# leds.net
KiCad netlist of a schematic drawn in Altium Designer
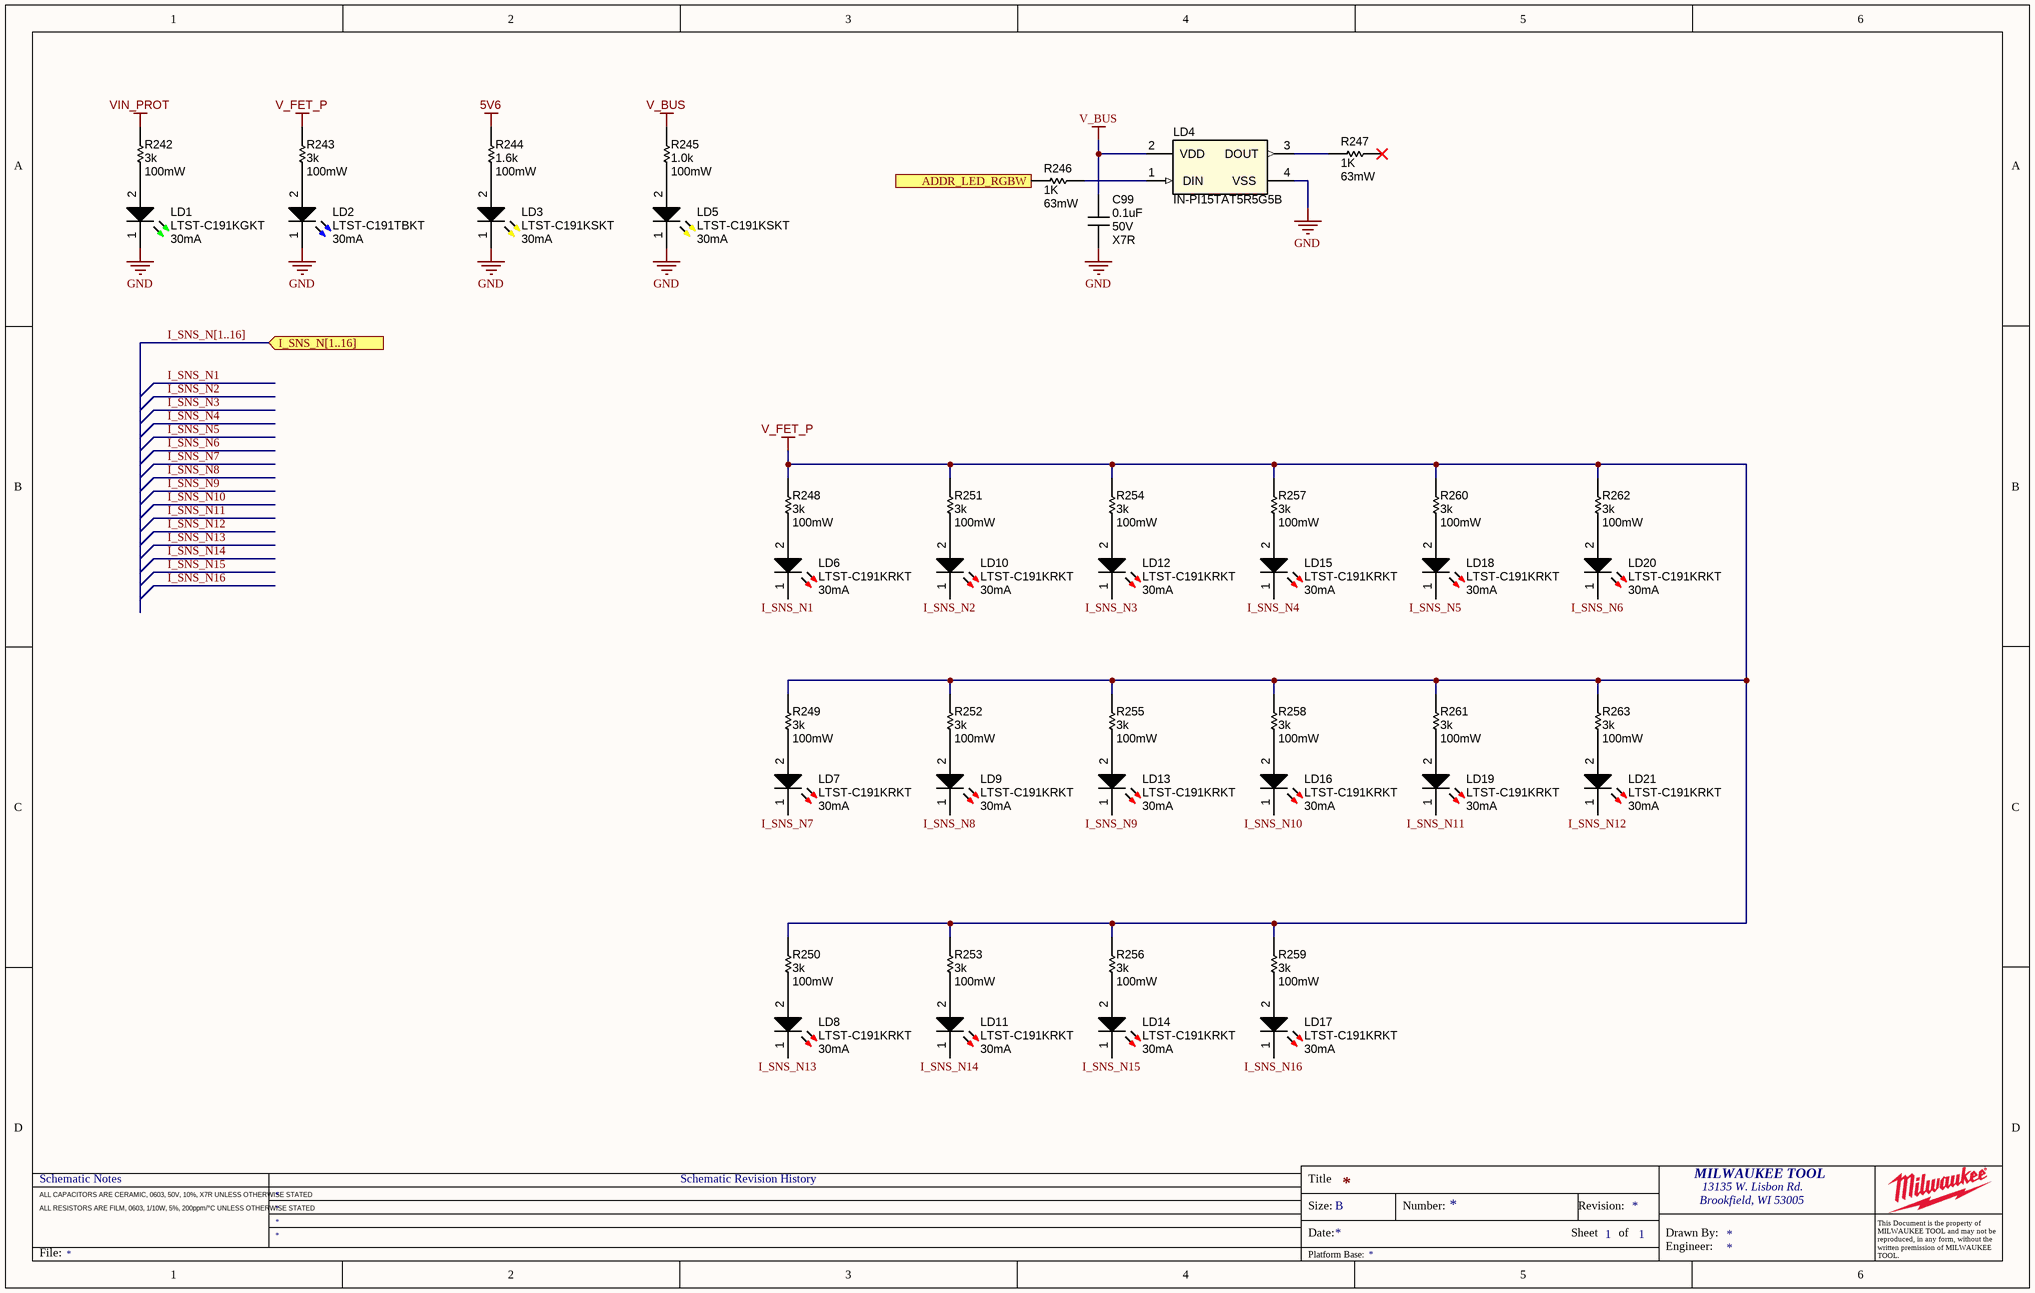
[diagram p0: leds.SchDoc]

(export (version "E")
  (design (tool "Eeschema 10.0.6"))
  (components
    (comp (ref "C99")
      (value "0.1uF")
      (footprint "CAPC1005X06N")
      (description "CAP CER SMD 0.1UF 50V X7R 0402")
      (fields
        (field (name "TOLERANCE") "10%")
        (field (name "MFR") "Murata Electronics")
        (field (name "VOLTAGE RATING") "50V")
        (field (name "TEMP COEFF") "X7R")
      )
      (libsource (lib "General_Library") (part "CMP-004-0076"))
    )
    (comp (ref "LD1")
      (value "LTST-C191KGKT")
      (footprint "LED_0603_GREEN")
      (description "LED GREEN CLEAR 0603 SMD")
      (fields
        (field (name "MFR") "Lite-On Inc.")
        (field (name "VOLTAGE") "2V")
        (field (name "CURRENT RATING") "30mA")
      )
      (libsource (lib "General_Library") (part "CMP-012-0014"))
    )
    (comp (ref "LD2")
      (value "LTST-C191TBKT")
      (footprint "LED_0603_BLUE")
      (description "LED BLUE CLEAR 0603 SMD")
      (fields
        (field (name "MFR") "Lite-On Inc.")
        (field (name "VOLTAGE") "2V")
        (field (name "CURRENT RATING") "30mA")
      )
      (libsource (lib "General_Library") (part "CMP-012-0016"))
    )
    (comp (ref "LD3")
      (value "LTST-C191KSKT")
      (footprint "LED_0603_YELLOW")
      (description "LED YELLOW CLEAR 0603 SMD")
      (fields
        (field (name "MFR") "Lite-On Inc.")
        (field (name "VOLTAGE") "2V")
        (field (name "CURRENT RATING") "30mA")
      )
      (libsource (lib "General_Library") (part "CMP-012-0015"))
    )
    (comp (ref "LD4")
      (value "IN-PI15TAT5R5G5B")
      (footprint "LED_INOLUX_IN-PI15TAT5R5G5B")
      (description "LED ADDRESSABLE RGB 1.50mm x 1.50mm")
      (fields (field (name "MFR") "Inolux"))
      (libsource (lib "General_Library") (part "CMP-012-0023"))
    )
    (comp (ref "LD5")
      (value "LTST-C191KSKT")
      (footprint "LED_0603_YELLOW")
      (description "LED YELLOW CLEAR 0603 SMD")
      (fields
        (field (name "MFR") "Lite-On Inc.")
        (field (name "VOLTAGE") "2V")
        (field (name "CURRENT RATING") "30mA")
      )
      (libsource (lib "General_Library") (part "CMP-012-0015"))
    )
    (comp (ref "LD6")
      (value "LTST-C191KRKT")
      (footprint "LED_0603_RED")
      (description "LED RED CLEAR 0603 SMD")
      (fields
        (field (name "MFR") "Lite-On Inc.")
        (field (name "VOLTAGE") "2V")
        (field (name "CURRENT RATING") "30mA")
      )
      (libsource (lib "General_Library") (part "CMP-012-0013"))
    )
    (comp (ref "LD7")
      (value "LTST-C191KRKT")
      (footprint "LED_0603_RED")
      (description "LED RED CLEAR 0603 SMD")
      (fields
        (field (name "MFR") "Lite-On Inc.")
        (field (name "VOLTAGE") "2V")
        (field (name "CURRENT RATING") "30mA")
      )
      (libsource (lib "General_Library") (part "CMP-012-0013"))
    )
    (comp (ref "LD8")
      (value "LTST-C191KRKT")
      (footprint "LED_0603_RED")
      (description "LED RED CLEAR 0603 SMD")
      (fields
        (field (name "MFR") "Lite-On Inc.")
        (field (name "VOLTAGE") "2V")
        (field (name "CURRENT RATING") "30mA")
      )
      (libsource (lib "General_Library") (part "CMP-012-0013"))
    )
    (comp (ref "LD9")
      (value "LTST-C191KRKT")
      (footprint "LED_0603_RED")
      (description "LED RED CLEAR 0603 SMD")
      (fields
        (field (name "MFR") "Lite-On Inc.")
        (field (name "VOLTAGE") "2V")
        (field (name "CURRENT RATING") "30mA")
      )
      (libsource (lib "General_Library") (part "CMP-012-0013"))
    )
    (comp (ref "LD10")
      (value "LTST-C191KRKT")
      (footprint "LED_0603_RED")
      (description "LED RED CLEAR 0603 SMD")
      (fields
        (field (name "MFR") "Lite-On Inc.")
        (field (name "VOLTAGE") "2V")
        (field (name "CURRENT RATING") "30mA")
      )
      (libsource (lib "General_Library") (part "CMP-012-0013"))
    )
    (comp (ref "LD11")
      (value "LTST-C191KRKT")
      (footprint "LED_0603_RED")
      (description "LED RED CLEAR 0603 SMD")
      (fields
        (field (name "MFR") "Lite-On Inc.")
        (field (name "VOLTAGE") "2V")
        (field (name "CURRENT RATING") "30mA")
      )
      (libsource (lib "General_Library") (part "CMP-012-0013"))
    )
    (comp (ref "LD12")
      (value "LTST-C191KRKT")
      (footprint "LED_0603_RED")
      (description "LED RED CLEAR 0603 SMD")
      (fields
        (field (name "MFR") "Lite-On Inc.")
        (field (name "VOLTAGE") "2V")
        (field (name "CURRENT RATING") "30mA")
      )
      (libsource (lib "General_Library") (part "CMP-012-0013"))
    )
    (comp (ref "LD13")
      (value "LTST-C191KRKT")
      (footprint "LED_0603_RED")
      (description "LED RED CLEAR 0603 SMD")
      (fields
        (field (name "MFR") "Lite-On Inc.")
        (field (name "VOLTAGE") "2V")
        (field (name "CURRENT RATING") "30mA")
      )
      (libsource (lib "General_Library") (part "CMP-012-0013"))
    )
    (comp (ref "LD14")
      (value "LTST-C191KRKT")
      (footprint "LED_0603_RED")
      (description "LED RED CLEAR 0603 SMD")
      (fields
        (field (name "MFR") "Lite-On Inc.")
        (field (name "VOLTAGE") "2V")
        (field (name "CURRENT RATING") "30mA")
      )
      (libsource (lib "General_Library") (part "CMP-012-0013"))
    )
    (comp (ref "LD15")
      (value "LTST-C191KRKT")
      (footprint "LED_0603_RED")
      (description "LED RED CLEAR 0603 SMD")
      (fields
        (field (name "MFR") "Lite-On Inc.")
        (field (name "VOLTAGE") "2V")
        (field (name "CURRENT RATING") "30mA")
      )
      (libsource (lib "General_Library") (part "CMP-012-0013"))
    )
    (comp (ref "LD16")
      (value "LTST-C191KRKT")
      (footprint "LED_0603_RED")
      (description "LED RED CLEAR 0603 SMD")
      (fields
        (field (name "MFR") "Lite-On Inc.")
        (field (name "VOLTAGE") "2V")
        (field (name "CURRENT RATING") "30mA")
      )
      (libsource (lib "General_Library") (part "CMP-012-0013"))
    )
    (comp (ref "LD17")
      (value "LTST-C191KRKT")
      (footprint "LED_0603_RED")
      (description "LED RED CLEAR 0603 SMD")
      (fields
        (field (name "MFR") "Lite-On Inc.")
        (field (name "VOLTAGE") "2V")
        (field (name "CURRENT RATING") "30mA")
      )
      (libsource (lib "General_Library") (part "CMP-012-0013"))
    )
    (comp (ref "LD18")
      (value "LTST-C191KRKT")
      (footprint "LED_0603_RED")
      (description "LED RED CLEAR 0603 SMD")
      (fields
        (field (name "MFR") "Lite-On Inc.")
        (field (name "VOLTAGE") "2V")
        (field (name "CURRENT RATING") "30mA")
      )
      (libsource (lib "General_Library") (part "CMP-012-0013"))
    )
    (comp (ref "LD19")
      (value "LTST-C191KRKT")
      (footprint "LED_0603_RED")
      (description "LED RED CLEAR 0603 SMD")
      (fields
        (field (name "MFR") "Lite-On Inc.")
        (field (name "VOLTAGE") "2V")
        (field (name "CURRENT RATING") "30mA")
      )
      (libsource (lib "General_Library") (part "CMP-012-0013"))
    )
    (comp (ref "LD20")
      (value "LTST-C191KRKT")
      (footprint "LED_0603_RED")
      (description "LED RED CLEAR 0603 SMD")
      (fields
        (field (name "MFR") "Lite-On Inc.")
        (field (name "VOLTAGE") "2V")
        (field (name "CURRENT RATING") "30mA")
      )
      (libsource (lib "General_Library") (part "CMP-012-0013"))
    )
    (comp (ref "LD21")
      (value "LTST-C191KRKT")
      (footprint "LED_0603_RED")
      (description "LED RED CLEAR 0603 SMD")
      (fields
        (field (name "MFR") "Lite-On Inc.")
        (field (name "VOLTAGE") "2V")
        (field (name "CURRENT RATING") "30mA")
      )
      (libsource (lib "General_Library") (part "CMP-012-0013"))
    )
    (comp (ref "R242")
      (value "3k")
      (footprint "RESC1608X06N")
      (description "RES SMD 3K OHM 1% 1/10W 0603")
      (fields
        (field (name "MFR") "Panasonic Electronic Components")
        (field (name "TOLERANCE") "1%")
        (field (name "WATTAGE") "100mW")
      )
      (libsource (lib "General_Library") (part "CMP-025-0012"))
    )
    (comp (ref "R243")
      (value "3k")
      (footprint "RESC1608X06N")
      (description "RES SMD 3K OHM 1% 1/10W 0603")
      (fields
        (field (name "MFR") "Panasonic Electronic Components")
        (field (name "TOLERANCE") "1%")
        (field (name "WATTAGE") "100mW")
      )
      (libsource (lib "General_Library") (part "CMP-025-0012"))
    )
    (comp (ref "R244")
      (value "1.6k")
      (footprint "RESC1608X06N")
      (description "RES SMD 1.6K OHM 1% 1/10W 0603")
      (fields
        (field (name "MFR") "Stackpole Electronics Inc")
        (field (name "TOLERANCE") "1%")
        (field (name "WATTAGE") "100mW")
      )
      (libsource (lib "General_Library") (part "CMP-025-0060"))
    )
    (comp (ref "R245")
      (value "1.0k")
      (footprint "RESC1608X06N")
      (description "RES SMD 1K OHM 1% 1/10W 0603")
      (fields
        (field (name "MFR") "Panasonic Electronic Components")
        (field (name "VOLTAGE") "75V")
        (field (name "WATTAGE") "100mW")
      )
      (libsource (lib "General_Library") (part "CMP-025-0097"))
    )
    (comp (ref "R246")
      (value "1K")
      (footprint "RESC1005X04N")
      (description "RES SMD 1K OHM 1% 1/16W 0402")
      (fields
        (field (name "TOLERANCE") "1%")
        (field (name "MFR") "Stackpole Electronics Inc")
        (field (name "WATTAGE") "63mW")
      )
      (libsource (lib "General_Library") (part "CMP-025-0154"))
    )
    (comp (ref "R247")
      (value "1K")
      (footprint "RESC1005X04N")
      (description "RES SMD 1K OHM 1% 1/16W 0402")
      (fields
        (field (name "TOLERANCE") "1%")
        (field (name "MFR") "Stackpole Electronics Inc")
        (field (name "WATTAGE") "63mW")
      )
      (libsource (lib "General_Library") (part "CMP-025-0154"))
    )
    (comp (ref "R248")
      (value "3k")
      (footprint "RESC1608X06N")
      (description "RES SMD 3K OHM 1% 1/10W 0603")
      (fields
        (field (name "MFR") "Panasonic Electronic Components")
        (field (name "TOLERANCE") "1%")
        (field (name "WATTAGE") "100mW")
      )
      (libsource (lib "General_Library") (part "CMP-025-0012"))
    )
    (comp (ref "R249")
      (value "3k")
      (footprint "RESC1608X06N")
      (description "RES SMD 3K OHM 1% 1/10W 0603")
      (fields
        (field (name "MFR") "Panasonic Electronic Components")
        (field (name "TOLERANCE") "1%")
        (field (name "WATTAGE") "100mW")
      )
      (libsource (lib "General_Library") (part "CMP-025-0012"))
    )
    (comp (ref "R250")
      (value "3k")
      (footprint "RESC1608X06N")
      (description "RES SMD 3K OHM 1% 1/10W 0603")
      (fields
        (field (name "MFR") "Panasonic Electronic Components")
        (field (name "TOLERANCE") "1%")
        (field (name "WATTAGE") "100mW")
      )
      (libsource (lib "General_Library") (part "CMP-025-0012"))
    )
    (comp (ref "R251")
      (value "3k")
      (footprint "RESC1608X06N")
      (description "RES SMD 3K OHM 1% 1/10W 0603")
      (fields
        (field (name "MFR") "Panasonic Electronic Components")
        (field (name "TOLERANCE") "1%")
        (field (name "WATTAGE") "100mW")
      )
      (libsource (lib "General_Library") (part "CMP-025-0012"))
    )
    (comp (ref "R252")
      (value "3k")
      (footprint "RESC1608X06N")
      (description "RES SMD 3K OHM 1% 1/10W 0603")
      (fields
        (field (name "MFR") "Panasonic Electronic Components")
        (field (name "TOLERANCE") "1%")
        (field (name "WATTAGE") "100mW")
      )
      (libsource (lib "General_Library") (part "CMP-025-0012"))
    )
    (comp (ref "R253")
      (value "3k")
      (footprint "RESC1608X06N")
      (description "RES SMD 3K OHM 1% 1/10W 0603")
      (fields
        (field (name "MFR") "Panasonic Electronic Components")
        (field (name "TOLERANCE") "1%")
        (field (name "WATTAGE") "100mW")
      )
      (libsource (lib "General_Library") (part "CMP-025-0012"))
    )
    (comp (ref "R254")
      (value "3k")
      (footprint "RESC1608X06N")
      (description "RES SMD 3K OHM 1% 1/10W 0603")
      (fields
        (field (name "MFR") "Panasonic Electronic Components")
        (field (name "TOLERANCE") "1%")
        (field (name "WATTAGE") "100mW")
      )
      (libsource (lib "General_Library") (part "CMP-025-0012"))
    )
    (comp (ref "R255")
      (value "3k")
      (footprint "RESC1608X06N")
      (description "RES SMD 3K OHM 1% 1/10W 0603")
      (fields
        (field (name "MFR") "Panasonic Electronic Components")
        (field (name "TOLERANCE") "1%")
        (field (name "WATTAGE") "100mW")
      )
      (libsource (lib "General_Library") (part "CMP-025-0012"))
    )
    (comp (ref "R256")
      (value "3k")
      (footprint "RESC1608X06N")
      (description "RES SMD 3K OHM 1% 1/10W 0603")
      (fields
        (field (name "MFR") "Panasonic Electronic Components")
        (field (name "TOLERANCE") "1%")
        (field (name "WATTAGE") "100mW")
      )
      (libsource (lib "General_Library") (part "CMP-025-0012"))
    )
    (comp (ref "R257")
      (value "3k")
      (footprint "RESC1608X06N")
      (description "RES SMD 3K OHM 1% 1/10W 0603")
      (fields
        (field (name "MFR") "Panasonic Electronic Components")
        (field (name "TOLERANCE") "1%")
        (field (name "WATTAGE") "100mW")
      )
      (libsource (lib "General_Library") (part "CMP-025-0012"))
    )
    (comp (ref "R258")
      (value "3k")
      (footprint "RESC1608X06N")
      (description "RES SMD 3K OHM 1% 1/10W 0603")
      (fields
        (field (name "MFR") "Panasonic Electronic Components")
        (field (name "TOLERANCE") "1%")
        (field (name "WATTAGE") "100mW")
      )
      (libsource (lib "General_Library") (part "CMP-025-0012"))
    )
    (comp (ref "R259")
      (value "3k")
      (footprint "RESC1608X06N")
      (description "RES SMD 3K OHM 1% 1/10W 0603")
      (fields
        (field (name "MFR") "Panasonic Electronic Components")
        (field (name "TOLERANCE") "1%")
        (field (name "WATTAGE") "100mW")
      )
      (libsource (lib "General_Library") (part "CMP-025-0012"))
    )
    (comp (ref "R260")
      (value "3k")
      (footprint "RESC1608X06N")
      (description "RES SMD 3K OHM 1% 1/10W 0603")
      (fields
        (field (name "MFR") "Panasonic Electronic Components")
        (field (name "TOLERANCE") "1%")
        (field (name "WATTAGE") "100mW")
      )
      (libsource (lib "General_Library") (part "CMP-025-0012"))
    )
    (comp (ref "R261")
      (value "3k")
      (footprint "RESC1608X06N")
      (description "RES SMD 3K OHM 1% 1/10W 0603")
      (fields
        (field (name "MFR") "Panasonic Electronic Components")
        (field (name "TOLERANCE") "1%")
        (field (name "WATTAGE") "100mW")
      )
      (libsource (lib "General_Library") (part "CMP-025-0012"))
    )
    (comp (ref "R262")
      (value "3k")
      (footprint "RESC1608X06N")
      (description "RES SMD 3K OHM 1% 1/10W 0603")
      (fields
        (field (name "MFR") "Panasonic Electronic Components")
        (field (name "TOLERANCE") "1%")
        (field (name "WATTAGE") "100mW")
      )
      (libsource (lib "General_Library") (part "CMP-025-0012"))
    )
    (comp (ref "R263")
      (value "3k")
      (footprint "RESC1608X06N")
      (description "RES SMD 3K OHM 1% 1/10W 0603")
      (fields
        (field (name "MFR") "Panasonic Electronic Components")
        (field (name "TOLERANCE") "1%")
        (field (name "WATTAGE") "100mW")
      )
      (libsource (lib "General_Library") (part "CMP-025-0012"))
    )
  )
  (nets
    (net (code "1") (name "/ADDR_LED_RGBW") (class "Default")
      (node (ref "R246") (pin "1") (pinfunction "1_1") (pintype "passive"))
    )
    (net (code "2") (name "/I_SNS_N1") (class "Default")
      (node (ref "LD6") (pin "1") (pinfunction "K_1") (pintype "passive"))
    )
    (net (code "3") (name "/I_SNS_N2") (class "Default")
      (node (ref "LD10") (pin "1") (pinfunction "K_1") (pintype "passive"))
    )
    (net (code "4") (name "/I_SNS_N3") (class "Default")
      (node (ref "LD12") (pin "1") (pinfunction "K_1") (pintype "passive"))
    )
    (net (code "5") (name "/I_SNS_N4") (class "Default")
      (node (ref "LD15") (pin "1") (pinfunction "K_1") (pintype "passive"))
    )
    (net (code "6") (name "/I_SNS_N5") (class "Default")
      (node (ref "LD18") (pin "1") (pinfunction "K_1") (pintype "passive"))
    )
    (net (code "7") (name "/I_SNS_N6") (class "Default")
      (node (ref "LD20") (pin "1") (pinfunction "K_1") (pintype "passive"))
    )
    (net (code "8") (name "/I_SNS_N7") (class "Default")
      (node (ref "LD7") (pin "1") (pinfunction "K_1") (pintype "passive"))
    )
    (net (code "9") (name "/I_SNS_N8") (class "Default")
      (node (ref "LD9") (pin "1") (pinfunction "K_1") (pintype "passive"))
    )
    (net (code "10") (name "/I_SNS_N9") (class "Default")
      (node (ref "LD13") (pin "1") (pinfunction "K_1") (pintype "passive"))
    )
    (net (code "11") (name "/I_SNS_N10") (class "Default")
      (node (ref "LD16") (pin "1") (pinfunction "K_1") (pintype "passive"))
    )
    (net (code "12") (name "/I_SNS_N11") (class "Default")
      (node (ref "LD19") (pin "1") (pinfunction "K_1") (pintype "passive"))
    )
    (net (code "13") (name "/I_SNS_N12") (class "Default")
      (node (ref "LD21") (pin "1") (pinfunction "K_1") (pintype "passive"))
    )
    (net (code "14") (name "/I_SNS_N13") (class "Default")
      (node (ref "LD8") (pin "1") (pinfunction "K_1") (pintype "passive"))
    )
    (net (code "15") (name "/I_SNS_N14") (class "Default")
      (node (ref "LD11") (pin "1") (pinfunction "K_1") (pintype "passive"))
    )
    (net (code "16") (name "/I_SNS_N15") (class "Default")
      (node (ref "LD14") (pin "1") (pinfunction "K_1") (pintype "passive"))
    )
    (net (code "17") (name "/I_SNS_N16") (class "Default")
      (node (ref "LD17") (pin "1") (pinfunction "K_1") (pintype "passive"))
    )
    (net (code "19") (name "5V6") (class "Default")
      (node (ref "R244") (pin "2") (pinfunction "2_2") (pintype "passive"))
    )
    (net (code "20") (name "GND") (class "Default")
      (node (ref "C99") (pin "2") (pinfunction "2_2") (pintype "passive"))
      (node (ref "LD1") (pin "1") (pinfunction "K_1") (pintype "passive"))
      (node (ref "LD2") (pin "1") (pinfunction "K_1") (pintype "passive"))
      (node (ref "LD3") (pin "1") (pinfunction "K_1") (pintype "passive"))
      (node (ref "LD4") (pin "4") (pinfunction "VSS_4") (pintype "power_in"))
      (node (ref "LD5") (pin "1") (pinfunction "K_1") (pintype "passive"))
    )
    (net (code "21") (name "Net-(LD1-A)") (class "Default")
      (node (ref "LD1") (pin "2") (pinfunction "A_2") (pintype "passive"))
      (node (ref "R242") (pin "1") (pinfunction "1_1") (pintype "passive"))
    )
    (net (code "22") (name "Net-(LD2-A)") (class "Default")
      (node (ref "LD2") (pin "2") (pinfunction "A_2") (pintype "passive"))
      (node (ref "R243") (pin "1") (pinfunction "1_1") (pintype "passive"))
    )
    (net (code "23") (name "Net-(LD3-A)") (class "Default")
      (node (ref "LD3") (pin "2") (pinfunction "A_2") (pintype "passive"))
      (node (ref "R244") (pin "1") (pinfunction "1_1") (pintype "passive"))
    )
    (net (code "24") (name "Net-(LD4-DIN)") (class "Default")
      (node (ref "LD4") (pin "1") (pinfunction "DIN_1") (pintype "input"))
      (node (ref "R246") (pin "2") (pinfunction "2_2") (pintype "passive"))
    )
    (net (code "25") (name "Net-(LD4-DOUT)") (class "Default")
      (node (ref "LD4") (pin "3") (pinfunction "DOUT_3") (pintype "output"))
      (node (ref "R247") (pin "1") (pinfunction "1_1") (pintype "passive"))
    )
    (net (code "26") (name "Net-(LD5-A)") (class "Default")
      (node (ref "LD5") (pin "2") (pinfunction "A_2") (pintype "passive"))
      (node (ref "R245") (pin "1") (pinfunction "1_1") (pintype "passive"))
    )
    (net (code "27") (name "Net-(LD6-A)") (class "Default")
      (node (ref "LD6") (pin "2") (pinfunction "A_2") (pintype "passive"))
      (node (ref "R248") (pin "1") (pinfunction "1_1") (pintype "passive"))
    )
    (net (code "28") (name "Net-(LD7-A)") (class "Default")
      (node (ref "LD7") (pin "2") (pinfunction "A_2") (pintype "passive"))
      (node (ref "R249") (pin "1") (pinfunction "1_1") (pintype "passive"))
    )
    (net (code "29") (name "Net-(LD8-A)") (class "Default")
      (node (ref "LD8") (pin "2") (pinfunction "A_2") (pintype "passive"))
      (node (ref "R250") (pin "1") (pinfunction "1_1") (pintype "passive"))
    )
    (net (code "30") (name "Net-(LD9-A)") (class "Default")
      (node (ref "LD9") (pin "2") (pinfunction "A_2") (pintype "passive"))
      (node (ref "R252") (pin "1") (pinfunction "1_1") (pintype "passive"))
    )
    (net (code "31") (name "Net-(LD10-A)") (class "Default")
      (node (ref "LD10") (pin "2") (pinfunction "A_2") (pintype "passive"))
      (node (ref "R251") (pin "1") (pinfunction "1_1") (pintype "passive"))
    )
    (net (code "32") (name "Net-(LD11-A)") (class "Default")
      (node (ref "LD11") (pin "2") (pinfunction "A_2") (pintype "passive"))
      (node (ref "R253") (pin "1") (pinfunction "1_1") (pintype "passive"))
    )
    (net (code "33") (name "Net-(LD12-A)") (class "Default")
      (node (ref "LD12") (pin "2") (pinfunction "A_2") (pintype "passive"))
      (node (ref "R254") (pin "1") (pinfunction "1_1") (pintype "passive"))
    )
    (net (code "34") (name "Net-(LD13-A)") (class "Default")
      (node (ref "LD13") (pin "2") (pinfunction "A_2") (pintype "passive"))
      (node (ref "R255") (pin "1") (pinfunction "1_1") (pintype "passive"))
    )
    (net (code "35") (name "Net-(LD14-A)") (class "Default")
      (node (ref "LD14") (pin "2") (pinfunction "A_2") (pintype "passive"))
      (node (ref "R256") (pin "1") (pinfunction "1_1") (pintype "passive"))
    )
    (net (code "36") (name "Net-(LD15-A)") (class "Default")
      (node (ref "LD15") (pin "2") (pinfunction "A_2") (pintype "passive"))
      (node (ref "R257") (pin "1") (pinfunction "1_1") (pintype "passive"))
    )
    (net (code "37") (name "Net-(LD16-A)") (class "Default")
      (node (ref "LD16") (pin "2") (pinfunction "A_2") (pintype "passive"))
      (node (ref "R258") (pin "1") (pinfunction "1_1") (pintype "passive"))
    )
    (net (code "38") (name "Net-(LD17-A)") (class "Default")
      (node (ref "LD17") (pin "2") (pinfunction "A_2") (pintype "passive"))
      (node (ref "R259") (pin "1") (pinfunction "1_1") (pintype "passive"))
    )
    (net (code "39") (name "Net-(LD18-A)") (class "Default")
      (node (ref "LD18") (pin "2") (pinfunction "A_2") (pintype "passive"))
      (node (ref "R260") (pin "1") (pinfunction "1_1") (pintype "passive"))
    )
    (net (code "40") (name "Net-(LD19-A)") (class "Default")
      (node (ref "LD19") (pin "2") (pinfunction "A_2") (pintype "passive"))
      (node (ref "R261") (pin "1") (pinfunction "1_1") (pintype "passive"))
    )
    (net (code "41") (name "Net-(LD20-A)") (class "Default")
      (node (ref "LD20") (pin "2") (pinfunction "A_2") (pintype "passive"))
      (node (ref "R262") (pin "1") (pinfunction "1_1") (pintype "passive"))
    )
    (net (code "42") (name "Net-(LD21-A)") (class "Default")
      (node (ref "LD21") (pin "2") (pinfunction "A_2") (pintype "passive"))
      (node (ref "R263") (pin "1") (pinfunction "1_1") (pintype "passive"))
    )
    (net (code "43") (name "VIN_PROT") (class "Default")
      (node (ref "R242") (pin "2") (pinfunction "2_2") (pintype "passive"))
    )
    (net (code "44") (name "V_BUS") (class "Default")
      (node (ref "C99") (pin "1") (pinfunction "1_1") (pintype "passive"))
      (node (ref "LD4") (pin "2") (pinfunction "VDD_2") (pintype "power_in"))
      (node (ref "R245") (pin "2") (pinfunction "2_2") (pintype "passive"))
    )
    (net (code "45") (name "V_FET_P") (class "Default")
      (node (ref "R243") (pin "2") (pinfunction "2_2") (pintype "passive"))
      (node (ref "R248") (pin "2") (pinfunction "2_2") (pintype "passive"))
      (node (ref "R249") (pin "2") (pinfunction "2_2") (pintype "passive"))
      (node (ref "R250") (pin "2") (pinfunction "2_2") (pintype "passive"))
      (node (ref "R251") (pin "2") (pinfunction "2_2") (pintype "passive"))
      (node (ref "R252") (pin "2") (pinfunction "2_2") (pintype "passive"))
      (node (ref "R253") (pin "2") (pinfunction "2_2") (pintype "passive"))
      (node (ref "R254") (pin "2") (pinfunction "2_2") (pintype "passive"))
      (node (ref "R255") (pin "2") (pinfunction "2_2") (pintype "passive"))
      (node (ref "R256") (pin "2") (pinfunction "2_2") (pintype "passive"))
      (node (ref "R257") (pin "2") (pinfunction "2_2") (pintype "passive"))
      (node (ref "R258") (pin "2") (pinfunction "2_2") (pintype "passive"))
      (node (ref "R259") (pin "2") (pinfunction "2_2") (pintype "passive"))
      (node (ref "R260") (pin "2") (pinfunction "2_2") (pintype "passive"))
      (node (ref "R261") (pin "2") (pinfunction "2_2") (pintype "passive"))
      (node (ref "R262") (pin "2") (pinfunction "2_2") (pintype "passive"))
      (node (ref "R263") (pin "2") (pinfunction "2_2") (pintype "passive"))
    )
    (net (code "46") (name "unconnected-(R247-Pad2)") (class "Default")
      (node (ref "R247") (pin "2") (pinfunction "2_2") (pintype "passive+no_connect"))
    )
  )
)
